# x-IMU3-SA-AX.net
KiCad netlist of a schematic drawn in Altium Designer
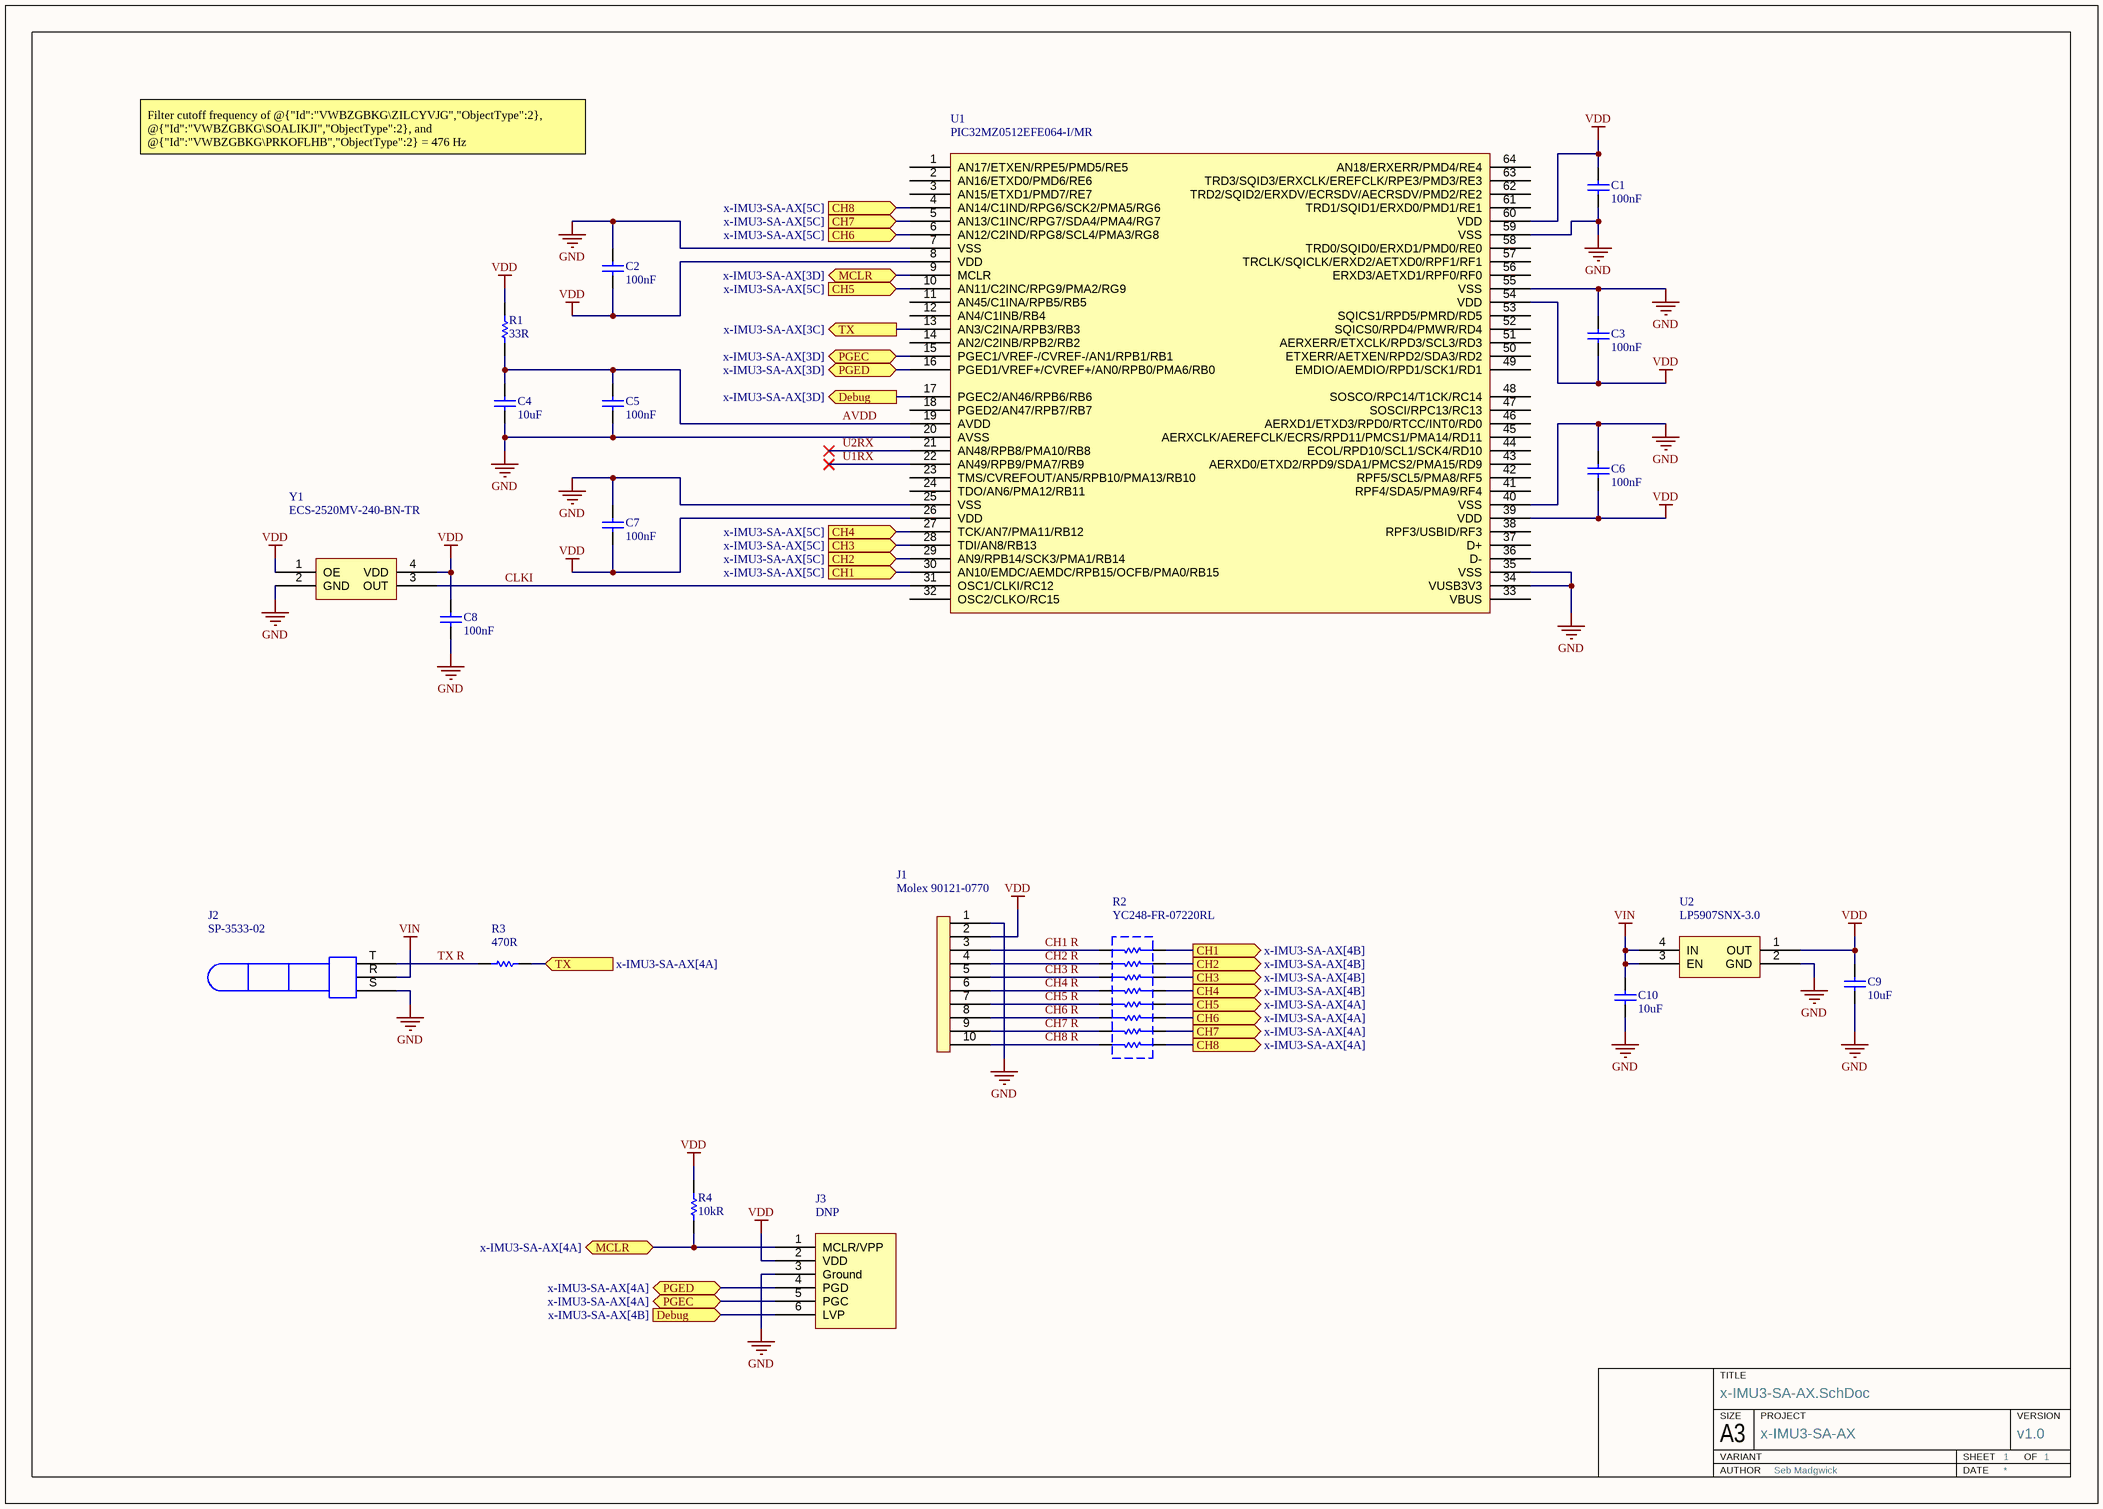
[diagram p0: x-IMU3-SA-AX.SchDoc]

(export (version "E")
  (design (tool "Eeschema 10.0.6"))
  (components
    (comp (ref "C1") (value "100nF") (footprint "Capacitor 0402") (libsource (lib "x-io") (part "Capacitor")))
    (comp (ref "C2") (value "100nF") (footprint "Capacitor 0402") (libsource (lib "x-io") (part "Capacitor")))
    (comp (ref "C3") (value "100nF") (footprint "Capacitor 0402") (libsource (lib "x-io") (part "Capacitor")))
    (comp (ref "C4") (value "10uF") (footprint "Capacitor 0402") (libsource (lib "x-io") (part "Capacitor")))
    (comp (ref "C5") (value "100nF") (footprint "Capacitor 0402") (libsource (lib "x-io") (part "Capacitor")))
    (comp (ref "C6") (value "100nF") (footprint "Capacitor 0402") (libsource (lib "x-io") (part "Capacitor")))
    (comp (ref "C7") (value "100nF") (footprint "Capacitor 0402") (libsource (lib "x-io") (part "Capacitor")))
    (comp (ref "C8") (value "100nF") (footprint "Capacitor 0402") (libsource (lib "x-io") (part "Capacitor")))
    (comp (ref "C9") (value "10uF") (footprint "Capacitor 0402") (libsource (lib "x-io") (part "Capacitor")))
    (comp (ref "C10") (value "10uF") (footprint "Capacitor 0402") (libsource (lib "x-io") (part "Capacitor")))
    (comp (ref "J1")
      (value "Molex 90121-0770")
      (footprint "Molex 90121-0770")
      (libsource (lib "x-io") (part "Molex 90121-0770"))
    )
    (comp (ref "J2")
      (value "SP-3533-02")
      (footprint "SP-3533-02")
      (libsource (lib "x-io") (part "SP-3533-02"))
    )
    (comp (ref "J3")
      (value "DNP")
      (footprint "Tag Connect No Legs")
      (libsource (lib "x-io") (part "MPLAB ICSP"))
    )
    (comp (ref "R1") (value "33R") (footprint "Resistor 0402") (libsource (lib "x-io") (part "Resistor")))
    (comp (ref "R2")
      (value "YC248-FR-07220RL")
      (footprint "YC248")
      (libsource (lib "x-io") (part "Resistor Array 8"))
    )
    (comp (ref "R3") (value "470R") (footprint "Resistor 0402") (libsource (lib "x-io") (part "Resistor")))
    (comp (ref "R4") (value "10kR") (footprint "Resistor 0402") (libsource (lib "x-io") (part "Resistor")))
    (comp (ref "U1")
      (value "PIC32MZ0512EFE064-I/MR")
      (footprint "QFN-64")
      (libsource (lib "x-io") (part "PIC32MZ2048EFH064"))
    )
    (comp (ref "U2")
      (value "LP5907SNX-3.0")
      (footprint "X2SON")
      (libsource (lib "x-io") (part "LP5907SNX-X.X"))
    )
    (comp (ref "Y1")
      (value "ECS-2520MV-240-BN-TR")
      (footprint "ECS 2x2.5mm")
      (libsource (lib "x-io") (part "Oscillator"))
    )
  )
  (nets
    (net (code "1") (name "/AVDD") (class "Default")
      (node (ref "C4") (pin "2") (pinfunction "2_2") (pintype "passive"))
      (node (ref "C5") (pin "2") (pinfunction "2_2") (pintype "passive"))
      (node (ref "R1") (pin "1") (pinfunction "1_1") (pintype "passive"))
      (node (ref "U1") (pin "19") (pinfunction "AVDD_19") (pintype "passive"))
    )
    (net (code "2") (name "/CH1") (class "Default")
      (node (ref "R2") (pin "1") (pinfunction "1_1") (pintype "passive"))
      (node (ref "U1") (pin "30") (pinfunction "AN10/EMDC/AEMDC/RPB15/OCFB/PMA0/RB15_30") (pintype "passive"))
    )
    (net (code "3") (name "/CH1 R") (class "Default")
      (node (ref "J1") (pin "3") (pinfunction "3_3") (pintype "passive"))
      (node (ref "R2") (pin "16") (pinfunction "16_16") (pintype "passive"))
    )
    (net (code "4") (name "/CH2") (class "Default")
      (node (ref "R2") (pin "2") (pinfunction "2_2") (pintype "passive"))
      (node (ref "U1") (pin "29") (pinfunction "AN9/RPB14/SCK3/PMA1/RB14_29") (pintype "passive"))
    )
    (net (code "5") (name "/CH2 R") (class "Default")
      (node (ref "J1") (pin "4") (pinfunction "4_4") (pintype "passive"))
      (node (ref "R2") (pin "15") (pinfunction "15_15") (pintype "passive"))
    )
    (net (code "6") (name "/CH3") (class "Default")
      (node (ref "R2") (pin "3") (pinfunction "3_3") (pintype "passive"))
      (node (ref "U1") (pin "28") (pinfunction "TDI/AN8/RB13_28") (pintype "passive"))
    )
    (net (code "7") (name "/CH3 R") (class "Default")
      (node (ref "J1") (pin "5") (pinfunction "5_5") (pintype "passive"))
      (node (ref "R2") (pin "14") (pinfunction "14_14") (pintype "passive"))
    )
    (net (code "8") (name "/CH4") (class "Default")
      (node (ref "R2") (pin "4") (pinfunction "4_4") (pintype "passive"))
      (node (ref "U1") (pin "27") (pinfunction "TCK/AN7/PMA11/RB12_27") (pintype "passive"))
    )
    (net (code "9") (name "/CH4 R") (class "Default")
      (node (ref "J1") (pin "6") (pinfunction "6_6") (pintype "passive"))
      (node (ref "R2") (pin "13") (pinfunction "13_13") (pintype "passive"))
    )
    (net (code "10") (name "/CH5") (class "Default")
      (node (ref "R2") (pin "5") (pinfunction "5_5") (pintype "passive"))
      (node (ref "U1") (pin "10") (pinfunction "AN11/C2INC/RPG9/PMA2/RG9_10") (pintype "passive"))
    )
    (net (code "11") (name "/CH5 R") (class "Default")
      (node (ref "J1") (pin "7") (pinfunction "7_7") (pintype "passive"))
      (node (ref "R2") (pin "12") (pinfunction "12_12") (pintype "passive"))
    )
    (net (code "12") (name "/CH6") (class "Default")
      (node (ref "R2") (pin "6") (pinfunction "6_6") (pintype "passive"))
      (node (ref "U1") (pin "6") (pinfunction "AN12/C2IND/RPG8/SCL4/PMA3/RG8_6") (pintype "passive"))
    )
    (net (code "13") (name "/CH6 R") (class "Default")
      (node (ref "J1") (pin "8") (pinfunction "8_8") (pintype "passive"))
      (node (ref "R2") (pin "11") (pinfunction "11_11") (pintype "passive"))
    )
    (net (code "14") (name "/CH7") (class "Default")
      (node (ref "R2") (pin "7") (pinfunction "7_7") (pintype "passive"))
      (node (ref "U1") (pin "5") (pinfunction "AN13/C1INC/RPG7/SDA4/PMA4/RG7_5") (pintype "passive"))
    )
    (net (code "15") (name "/CH7 R") (class "Default")
      (node (ref "J1") (pin "9") (pinfunction "9_9") (pintype "passive"))
      (node (ref "R2") (pin "10") (pinfunction "10_10") (pintype "passive"))
    )
    (net (code "16") (name "/CH8") (class "Default")
      (node (ref "R2") (pin "8") (pinfunction "8_8") (pintype "passive"))
      (node (ref "U1") (pin "4") (pinfunction "AN14/C1IND/RPG6/SCK2/PMA5/RG6_4") (pintype "passive"))
    )
    (net (code "17") (name "/CH8 R") (class "Default")
      (node (ref "J1") (pin "10") (pinfunction "10_10") (pintype "passive"))
      (node (ref "R2") (pin "9") (pinfunction "9_9") (pintype "passive"))
    )
    (net (code "18") (name "/CLKI") (class "Default")
      (node (ref "U1") (pin "31") (pinfunction "OSC1/CLKI/RC12_31") (pintype "passive"))
      (node (ref "Y1") (pin "3") (pinfunction "OUT_3") (pintype "passive"))
    )
    (net (code "19") (name "/Debug") (class "Default")
      (node (ref "J3") (pin "6") (pinfunction "LVP_6") (pintype "passive"))
      (node (ref "U1") (pin "17") (pinfunction "PGEC2/AN46/RPB6/RB6_17") (pintype "passive"))
    )
    (net (code "20") (name "/MCLR") (class "Default")
      (node (ref "J3") (pin "1") (pinfunction "MCLR/VPP_1") (pintype "passive"))
      (node (ref "R4") (pin "1") (pinfunction "1_1") (pintype "passive"))
      (node (ref "U1") (pin "9") (pinfunction "MCLR_9") (pintype "passive"))
    )
    (net (code "21") (name "/PGEC") (class "Default")
      (node (ref "J3") (pin "5") (pinfunction "PGC_5") (pintype "passive"))
      (node (ref "U1") (pin "15") (pinfunction "PGEC1/VREF-/CVREF-/AN1/RPB1/RB1_15") (pintype "passive"))
    )
    (net (code "22") (name "/PGED") (class "Default")
      (node (ref "J3") (pin "4") (pinfunction "PGD_4") (pintype "passive"))
      (node (ref "U1") (pin "16") (pinfunction "PGED1/VREF+/CVREF+/AN0/RPB0/PMA6/RB0_16") (pintype "passive"))
    )
    (net (code "23") (name "/TX") (class "Default")
      (node (ref "R3") (pin "2") (pinfunction "2_2") (pintype "passive"))
      (node (ref "U1") (pin "13") (pinfunction "AN3/C2INA/RPB3/RB3_13") (pintype "passive"))
    )
    (net (code "24") (name "/TX R") (class "Default")
      (node (ref "J2") (pin "T") (pinfunction "T_T") (pintype "passive"))
      (node (ref "R3") (pin "1") (pinfunction "1_1") (pintype "passive"))
    )
    (net (code "25") (name "/U1RX") (class "Default")
      (node (ref "U1") (pin "22") (pinfunction "AN49/RPB9/PMA7/RB9_22") (pintype "passive+no_connect"))
    )
    (net (code "26") (name "/U2RX") (class "Default")
      (node (ref "U1") (pin "21") (pinfunction "AN48/RPB8/PMA10/RB8_21") (pintype "passive+no_connect"))
    )
    (net (code "27") (name "GND") (class "Default")
      (node (ref "C1") (pin "1") (pinfunction "1_1") (pintype "passive"))
      (node (ref "C10") (pin "1") (pinfunction "1_1") (pintype "passive"))
      (node (ref "C2") (pin "2") (pinfunction "2_2") (pintype "passive"))
      (node (ref "C3") (pin "2") (pinfunction "2_2") (pintype "passive"))
      (node (ref "C4") (pin "1") (pinfunction "1_1") (pintype "passive"))
      (node (ref "C5") (pin "1") (pinfunction "1_1") (pintype "passive"))
      (node (ref "C6") (pin "2") (pinfunction "2_2") (pintype "passive"))
      (node (ref "C7") (pin "2") (pinfunction "2_2") (pintype "passive"))
      (node (ref "C8") (pin "1") (pinfunction "1_1") (pintype "passive"))
      (node (ref "C9") (pin "1") (pinfunction "1_1") (pintype "passive"))
      (node (ref "J1") (pin "1") (pinfunction "1_1") (pintype "passive"))
      (node (ref "J2") (pin "S") (pinfunction "S_S") (pintype "passive"))
      (node (ref "J3") (pin "3") (pinfunction "Ground_3") (pintype "passive"))
      (node (ref "U1") (pin "20") (pinfunction "AVSS_20") (pintype "passive"))
      (node (ref "U1") (pin "25") (pinfunction "VSS_25") (pintype "passive"))
      (node (ref "U1") (pin "34") (pinfunction "VUSB3V3_34") (pintype "passive"))
      (node (ref "U1") (pin "35") (pinfunction "VSS_35") (pintype "passive"))
      (node (ref "U1") (pin "40") (pinfunction "VSS_40") (pintype "passive"))
      (node (ref "U1") (pin "55") (pinfunction "VSS_55") (pintype "passive"))
      (node (ref "U1") (pin "59") (pinfunction "VSS_59") (pintype "passive"))
      (node (ref "U1") (pin "7") (pinfunction "VSS_7") (pintype "passive"))
      (node (ref "U2") (pin "2") (pinfunction "GND_2") (pintype "passive"))
      (node (ref "Y1") (pin "2") (pinfunction "GND_2") (pintype "passive"))
    )
    (net (code "28") (name "VDD") (class "Default")
      (node (ref "C1") (pin "2") (pinfunction "2_2") (pintype "passive"))
      (node (ref "C2") (pin "1") (pinfunction "1_1") (pintype "passive"))
      (node (ref "C3") (pin "1") (pinfunction "1_1") (pintype "passive"))
      (node (ref "C6") (pin "1") (pinfunction "1_1") (pintype "passive"))
      (node (ref "C7") (pin "1") (pinfunction "1_1") (pintype "passive"))
      (node (ref "C8") (pin "2") (pinfunction "2_2") (pintype "passive"))
      (node (ref "C9") (pin "2") (pinfunction "2_2") (pintype "passive"))
      (node (ref "J1") (pin "2") (pinfunction "2_2") (pintype "passive"))
      (node (ref "J3") (pin "2") (pinfunction "VDD_2") (pintype "passive"))
      (node (ref "R1") (pin "2") (pinfunction "2_2") (pintype "passive"))
      (node (ref "R4") (pin "2") (pinfunction "2_2") (pintype "passive"))
      (node (ref "U1") (pin "26") (pinfunction "VDD_26") (pintype "passive"))
      (node (ref "U1") (pin "39") (pinfunction "VDD_39") (pintype "passive"))
      (node (ref "U1") (pin "54") (pinfunction "VDD_54") (pintype "passive"))
      (node (ref "U1") (pin "60") (pinfunction "VDD_60") (pintype "passive"))
      (node (ref "U1") (pin "8") (pinfunction "VDD_8") (pintype "passive"))
      (node (ref "U2") (pin "1") (pinfunction "OUT_1") (pintype "passive"))
      (node (ref "Y1") (pin "1") (pinfunction "OE_1") (pintype "passive"))
      (node (ref "Y1") (pin "4") (pinfunction "VDD_4") (pintype "passive"))
    )
    (net (code "29") (name "VIN") (class "Default")
      (node (ref "C10") (pin "2") (pinfunction "2_2") (pintype "passive"))
      (node (ref "J2") (pin "R") (pinfunction "R_R") (pintype "passive"))
      (node (ref "U2") (pin "3") (pinfunction "EN_3") (pintype "passive"))
      (node (ref "U2") (pin "4") (pinfunction "IN_4") (pintype "passive"))
    )
    (net (code "30") (name "unconnected-(U1-AERXCLK{slash}AEREFCLK{slash}ECRS{slash}RPD11{slash}PMCS1{slash}PMA14{slash}RD11-Pad45)") (class "Default")
      (node (ref "U1") (pin "45") (pinfunction "AERXCLK/AEREFCLK/ECRS/RPD11/PMCS1/PMA14/RD11_45") (pintype "passive"))
    )
    (net (code "31") (name "unconnected-(U1-AERXD0{slash}ETXD2{slash}RPD9{slash}SDA1{slash}PMCS2{slash}PMA15{slash}RD9-Pad43)") (class "Default")
      (node (ref "U1") (pin "43") (pinfunction "AERXD0/ETXD2/RPD9/SDA1/PMCS2/PMA15/RD9_43") (pintype "passive"))
    )
    (net (code "32") (name "unconnected-(U1-AERXD1{slash}ETXD3{slash}RPD0{slash}RTCC{slash}INT0{slash}RD0-Pad46)") (class "Default")
      (node (ref "U1") (pin "46") (pinfunction "AERXD1/ETXD3/RPD0/RTCC/INT0/RD0_46") (pintype "passive"))
    )
    (net (code "33") (name "unconnected-(U1-AERXERR{slash}ETXCLK{slash}RPD3{slash}SCL3{slash}RD3-Pad51)") (class "Default")
      (node (ref "U1") (pin "51") (pinfunction "AERXERR/ETXCLK/RPD3/SCL3/RD3_51") (pintype "passive"))
    )
    (net (code "34") (name "unconnected-(U1-AN2{slash}C2INB{slash}RPB2{slash}RB2-Pad14)") (class "Default")
      (node (ref "U1") (pin "14") (pinfunction "AN2/C2INB/RPB2/RB2_14") (pintype "passive"))
    )
    (net (code "35") (name "unconnected-(U1-AN4{slash}C1INB{slash}RB4-Pad12)") (class "Default")
      (node (ref "U1") (pin "12") (pinfunction "AN4/C1INB/RB4_12") (pintype "passive"))
    )
    (net (code "36") (name "unconnected-(U1-AN15{slash}ETXD1{slash}PMD7{slash}RE7-Pad3)") (class "Default")
      (node (ref "U1") (pin "3") (pinfunction "AN15/ETXD1/PMD7/RE7_3") (pintype "passive"))
    )
    (net (code "37") (name "unconnected-(U1-AN16{slash}ETXD0{slash}PMD6{slash}RE6-Pad2)") (class "Default")
      (node (ref "U1") (pin "2") (pinfunction "AN16/ETXD0/PMD6/RE6_2") (pintype "passive"))
    )
    (net (code "38") (name "unconnected-(U1-AN17{slash}ETXEN{slash}RPE5{slash}PMD5{slash}RE5-Pad1)") (class "Default")
      (node (ref "U1") (pin "1") (pinfunction "AN17/ETXEN/RPE5/PMD5/RE5_1") (pintype "passive"))
    )
    (net (code "39") (name "unconnected-(U1-AN18{slash}ERXERR{slash}PMD4{slash}RE4-Pad64)") (class "Default")
      (node (ref "U1") (pin "64") (pinfunction "AN18/ERXERR/PMD4/RE4_64") (pintype "passive"))
    )
    (net (code "40") (name "unconnected-(U1-AN45{slash}C1INA{slash}RPB5{slash}RB5-Pad11)") (class "Default")
      (node (ref "U1") (pin "11") (pinfunction "AN45/C1INA/RPB5/RB5_11") (pintype "passive"))
    )
    (net (code "41") (name "unconnected-(U1-D+-Pad37)") (class "Default")
      (node (ref "U1") (pin "37") (pinfunction "D+_37") (pintype "passive"))
    )
    (net (code "42") (name "unconnected-(U1-D--Pad36)") (class "Default")
      (node (ref "U1") (pin "36") (pinfunction "D-_36") (pintype "passive"))
    )
    (net (code "43") (name "unconnected-(U1-ECOL{slash}RPD10{slash}SCL1{slash}SCK4{slash}RD10-Pad44)") (class "Default")
      (node (ref "U1") (pin "44") (pinfunction "ECOL/RPD10/SCL1/SCK4/RD10_44") (pintype "passive"))
    )
    (net (code "44") (name "unconnected-(U1-EMDIO{slash}AEMDIO{slash}RPD1{slash}SCK1{slash}RD1-Pad49)") (class "Default")
      (node (ref "U1") (pin "49") (pinfunction "EMDIO/AEMDIO/RPD1/SCK1/RD1_49") (pintype "passive"))
    )
    (net (code "45") (name "unconnected-(U1-ERXD3{slash}AETXD1{slash}RPF0{slash}RF0-Pad56)") (class "Default")
      (node (ref "U1") (pin "56") (pinfunction "ERXD3/AETXD1/RPF0/RF0_56") (pintype "passive"))
    )
    (net (code "46") (name "unconnected-(U1-ETXERR{slash}AETXEN{slash}RPD2{slash}SDA3{slash}RD2-Pad50)") (class "Default")
      (node (ref "U1") (pin "50") (pinfunction "ETXERR/AETXEN/RPD2/SDA3/RD2_50") (pintype "passive"))
    )
    (net (code "47") (name "unconnected-(U1-OSC2{slash}CLKO{slash}RC15-Pad32)") (class "Default")
      (node (ref "U1") (pin "32") (pinfunction "OSC2/CLKO/RC15_32") (pintype "passive"))
    )
    (net (code "48") (name "unconnected-(U1-PGED2{slash}AN47{slash}RPB7{slash}RB7-Pad18)") (class "Default")
      (node (ref "U1") (pin "18") (pinfunction "PGED2/AN47/RPB7/RB7_18") (pintype "passive"))
    )
    (net (code "49") (name "unconnected-(U1-RPF3{slash}USBID{slash}RF3-Pad38)") (class "Default")
      (node (ref "U1") (pin "38") (pinfunction "RPF3/USBID/RF3_38") (pintype "passive"))
    )
    (net (code "50") (name "unconnected-(U1-RPF4{slash}SDA5{slash}PMA9{slash}RF4-Pad41)") (class "Default")
      (node (ref "U1") (pin "41") (pinfunction "RPF4/SDA5/PMA9/RF4_41") (pintype "passive"))
    )
    (net (code "51") (name "unconnected-(U1-RPF5{slash}SCL5{slash}PMA8{slash}RF5-Pad42)") (class "Default")
      (node (ref "U1") (pin "42") (pinfunction "RPF5/SCL5/PMA8/RF5_42") (pintype "passive"))
    )
    (net (code "52") (name "unconnected-(U1-SOSCI{slash}RPC13{slash}RC13-Pad47)") (class "Default")
      (node (ref "U1") (pin "47") (pinfunction "SOSCI/RPC13/RC13_47") (pintype "passive"))
    )
    (net (code "53") (name "unconnected-(U1-SOSCO{slash}RPC14{slash}T1CK{slash}RC14-Pad48)") (class "Default")
      (node (ref "U1") (pin "48") (pinfunction "SOSCO/RPC14/T1CK/RC14_48") (pintype "passive"))
    )
    (net (code "54") (name "unconnected-(U1-SQICS0{slash}RPD4{slash}PMWR{slash}RD4-Pad52)") (class "Default")
      (node (ref "U1") (pin "52") (pinfunction "SQICS0/RPD4/PMWR/RD4_52") (pintype "passive"))
    )
    (net (code "55") (name "unconnected-(U1-SQICS1{slash}RPD5{slash}PMRD{slash}RD5-Pad53)") (class "Default")
      (node (ref "U1") (pin "53") (pinfunction "SQICS1/RPD5/PMRD/RD5_53") (pintype "passive"))
    )
    (net (code "56") (name "unconnected-(U1-TDO{slash}AN6{slash}PMA12{slash}RB11-Pad24)") (class "Default")
      (node (ref "U1") (pin "24") (pinfunction "TDO/AN6/PMA12/RB11_24") (pintype "passive"))
    )
    (net (code "57") (name "unconnected-(U1-TMS{slash}CVREFOUT{slash}AN5{slash}RPB10{slash}PMA13{slash}RB10-Pad23)") (class "Default")
      (node (ref "U1") (pin "23") (pinfunction "TMS/CVREFOUT/AN5/RPB10/PMA13/RB10_23") (pintype "passive"))
    )
    (net (code "58") (name "unconnected-(U1-TRCLK{slash}SQICLK{slash}ERXD2{slash}AETXD0{slash}RPF1{slash}RF1-Pad57)") (class "Default")
      (node (ref "U1") (pin "57") (pinfunction "TRCLK/SQICLK/ERXD2/AETXD0/RPF1/RF1_57") (pintype "passive"))
    )
    (net (code "59") (name "unconnected-(U1-TRD0{slash}SQID0{slash}ERXD1{slash}PMD0{slash}RE0-Pad58)") (class "Default")
      (node (ref "U1") (pin "58") (pinfunction "TRD0/SQID0/ERXD1/PMD0/RE0_58") (pintype "passive"))
    )
    (net (code "60") (name "unconnected-(U1-TRD1{slash}SQID1{slash}ERXD0{slash}PMD1{slash}RE1-Pad61)") (class "Default")
      (node (ref "U1") (pin "61") (pinfunction "TRD1/SQID1/ERXD0/PMD1/RE1_61") (pintype "passive"))
    )
    (net (code "61") (name "unconnected-(U1-TRD2{slash}SQID2{slash}ERXDV{slash}ECRSDV{slash}AECRSDV{slash}PMD2{slash}RE2-Pad62)") (class "Default")
      (node (ref "U1") (pin "62") (pinfunction "TRD2/SQID2/ERXDV/ECRSDV/AECRSDV/PMD2/RE2_62") (pintype "passive"))
    )
    (net (code "62") (name "unconnected-(U1-TRD3{slash}SQID3{slash}ERXCLK{slash}EREFCLK{slash}RPE3{slash}PMD3{slash}RE3-Pad63)") (class "Default")
      (node (ref "U1") (pin "63") (pinfunction "TRD3/SQID3/ERXCLK/EREFCLK/RPE3/PMD3/RE3_63") (pintype "passive"))
    )
    (net (code "63") (name "unconnected-(U1-VBUS-Pad33)") (class "Default")
      (node (ref "U1") (pin "33") (pinfunction "VBUS_33") (pintype "passive"))
    )
  )
)
